# YoctoBob_LPC1102.net
KiCad netlist of a schematic drawn in Altium Designer
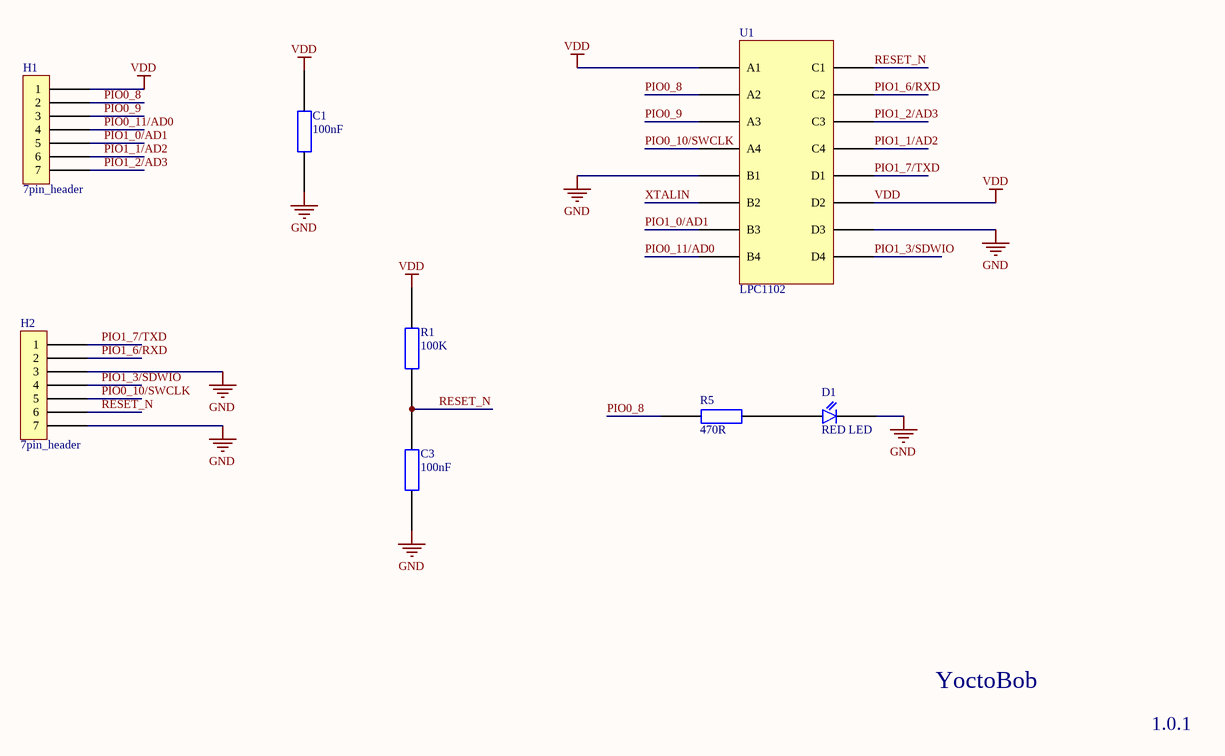
[diagram p0: YoctoBob_LPC1102.SchDoc]

(export (version "E")
  (design (tool "Eeschema 10.0.6"))
  (components
    (comp (ref "C1") (value "100nF") (footprint "C0805") (libsource (lib "Component_Library") (part "100nF")))
    (comp (ref "C3") (value "100nF") (footprint "C0805") (libsource (lib "Component_Library") (part "100nF")))
    (comp (ref "D1")
      (value "RED LED")
      (footprint "RED_LED_0805")
      (libsource (lib "Component_Library") (part "RED LED"))
    )
    (comp (ref "H1")
      (value "7pin_header")
      (footprint "HDR1X7")
      (libsource (lib "Component_Library") (part "7pin_header"))
    )
    (comp (ref "H2")
      (value "7pin_header")
      (footprint "HDR1X7")
      (libsource (lib "Component_Library") (part "7pin_header"))
    )
    (comp (ref "R1") (value "100K") (footprint "R0805") (libsource (lib "Component_Library") (part "100K")))
    (comp (ref "R5") (value "470R") (footprint "R0805") (libsource (lib "Component_Library") (part "470R")))
    (comp (ref "U1")
      (value "LPC1102")
      (footprint "BGA16x4")
      (libsource (lib "Component_Library") (part "LPC1102"))
    )
  )
  (nets
    (net (code "1") (name "/PIO0_8") (class "Default")
      (node (ref "H1") (pin "2") (pinfunction "2_2") (pintype "passive"))
      (node (ref "R5") (pin "1") (pinfunction "1_1") (pintype "passive"))
      (node (ref "U1") (pin "A2") (pinfunction "A2_A2") (pintype "passive"))
    )
    (net (code "2") (name "/PIO0_9") (class "Default")
      (node (ref "H1") (pin "3") (pinfunction "3_3") (pintype "passive"))
      (node (ref "U1") (pin "A3") (pinfunction "A3_A3") (pintype "passive"))
    )
    (net (code "3") (name "/PIO0_10{slash}SWCLK") (class "Default")
      (node (ref "H2") (pin "5") (pinfunction "5_5") (pintype "passive"))
      (node (ref "U1") (pin "A4") (pinfunction "A4_A4") (pintype "passive"))
    )
    (net (code "4") (name "/PIO0_11{slash}AD0") (class "Default")
      (node (ref "H1") (pin "4") (pinfunction "4_4") (pintype "passive"))
      (node (ref "U1") (pin "B4") (pinfunction "B4_B4") (pintype "passive"))
    )
    (net (code "5") (name "/PIO1_0{slash}AD1") (class "Default")
      (node (ref "H1") (pin "5") (pinfunction "5_5") (pintype "passive"))
      (node (ref "U1") (pin "B3") (pinfunction "B3_B3") (pintype "passive"))
    )
    (net (code "6") (name "/PIO1_1{slash}AD2") (class "Default")
      (node (ref "H1") (pin "6") (pinfunction "6_6") (pintype "passive"))
      (node (ref "U1") (pin "C4") (pinfunction "C4_C4") (pintype "passive"))
    )
    (net (code "7") (name "/PIO1_2{slash}AD3") (class "Default")
      (node (ref "H1") (pin "7") (pinfunction "7_7") (pintype "passive"))
      (node (ref "U1") (pin "C3") (pinfunction "C3_C3") (pintype "passive"))
    )
    (net (code "8") (name "/PIO1_3{slash}SDWIO") (class "Default")
      (node (ref "H2") (pin "4") (pinfunction "4_4") (pintype "passive"))
      (node (ref "U1") (pin "D4") (pinfunction "D4_D4") (pintype "passive"))
    )
    (net (code "9") (name "/PIO1_6{slash}RXD") (class "Default")
      (node (ref "H2") (pin "2") (pinfunction "2_2") (pintype "passive"))
      (node (ref "U1") (pin "C2") (pinfunction "C2_C2") (pintype "passive"))
    )
    (net (code "10") (name "/PIO1_7{slash}TXD") (class "Default")
      (node (ref "H2") (pin "1") (pinfunction "1_1") (pintype "passive"))
      (node (ref "U1") (pin "D1") (pinfunction "D1_D1") (pintype "passive"))
    )
    (net (code "11") (name "/RESET_N") (class "Default")
      (node (ref "C3") (pin "2") (pinfunction "2_2") (pintype "passive"))
      (node (ref "H2") (pin "6") (pinfunction "6_6") (pintype "passive"))
      (node (ref "R1") (pin "1") (pinfunction "1_1") (pintype "passive"))
      (node (ref "U1") (pin "C1") (pinfunction "C1_C1") (pintype "passive"))
    )
    (net (code "12") (name "/XTALIN") (class "Default")
      (node (ref "U1") (pin "B2") (pinfunction "B2_B2") (pintype "passive"))
    )
    (net (code "13") (name "GND") (class "Default")
      (node (ref "C1") (pin "1") (pinfunction "1_1") (pintype "passive"))
      (node (ref "C3") (pin "1") (pinfunction "1_1") (pintype "passive"))
      (node (ref "D1") (pin "2") (pinfunction "2_2") (pintype "passive"))
      (node (ref "H2") (pin "3") (pinfunction "3_3") (pintype "passive"))
      (node (ref "H2") (pin "7") (pinfunction "7_7") (pintype "passive"))
      (node (ref "U1") (pin "B1") (pinfunction "B1_B1") (pintype "passive"))
      (node (ref "U1") (pin "D3") (pinfunction "D3_D3") (pintype "passive"))
    )
    (net (code "14") (name "Net-(D1-Pad1)") (class "Default")
      (node (ref "D1") (pin "1") (pinfunction "1_1") (pintype "passive"))
      (node (ref "R5") (pin "2") (pinfunction "2_2") (pintype "passive"))
    )
    (net (code "15") (name "VDD") (class "Default")
      (node (ref "C1") (pin "2") (pinfunction "2_2") (pintype "passive"))
      (node (ref "H1") (pin "1") (pinfunction "1_1") (pintype "passive"))
      (node (ref "R1") (pin "2") (pinfunction "2_2") (pintype "passive"))
      (node (ref "U1") (pin "A1") (pinfunction "A1_A1") (pintype "passive"))
      (node (ref "U1") (pin "D2") (pinfunction "D2_D2") (pintype "passive"))
    )
  )
)
